# fakealarm_smd.net
KiCad netlist of a schematic drawn in EAGLE
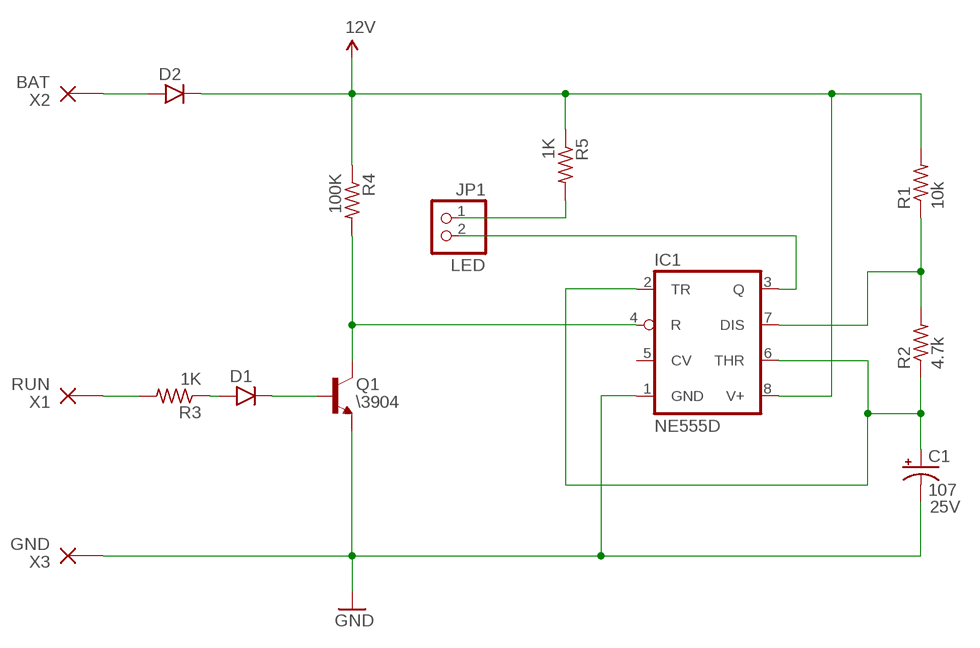
[diagram p0: schematic, sheet 1]

(export (version "E")
  (design (tool "Eeschema 10.0.6"))
  (components
    (comp (ref "C1")
      (value "107")
      (footprint "eagle-import:PANASONIC_C")
      (fields (field (name "VOLTAGE") "25V"))
      (libsource (lib "eagle-import") (part "CPOL-USC"))
    )
    (comp (ref "D1")
      (value "DIODE_SOD123FL")
      (footprint "eagle-import:SOD123FL")
      (libsource (lib "eagle-import") (part "DIODE_SOD123FL"))
    )
    (comp (ref "D2")
      (value "DIODE_SOD123FL")
      (footprint "eagle-import:SOD123FL")
      (libsource (lib "eagle-import") (part "DIODE_SOD123FL"))
    )
    (comp (ref "IC1")
      (value "NE555D")
      (footprint "eagle-import:SO08")
      (libsource (lib "eagle-import") (part "555DNE"))
    )
    (comp (ref "JP1")
      (value "LED")
      (footprint "eagle-import:1X02-S")
      (libsource (lib "eagle-import") (part "PINHD-1X02_2.54-S"))
    )
    (comp (ref "Q1")
      (value "\\3904")
      (footprint "eagle-import:SOT-23")
      (libsource (lib "eagle-import") (part "2N3904SOT23"))
    )
    (comp (ref "R1")
      (value "10k")
      (footprint "eagle-import:R0603")
      (libsource (lib "eagle-import") (part "R-US_R0603"))
    )
    (comp (ref "R2")
      (value "4.7k")
      (footprint "eagle-import:R0603")
      (libsource (lib "eagle-import") (part "R-US_R0603"))
    )
    (comp (ref "R3")
      (value "1K")
      (footprint "eagle-import:R0603")
      (libsource (lib "eagle-import") (part "R-US_R0603"))
    )
    (comp (ref "R4")
      (value "100K")
      (footprint "eagle-import:R0603")
      (libsource (lib "eagle-import") (part "R-US_R0603"))
    )
    (comp (ref "R5")
      (value "1K")
      (footprint "eagle-import:R0603")
      (libsource (lib "eagle-import") (part "R-US_R0603"))
    )
    (comp (ref "X1")
      (value "RUN")
      (footprint "eagle-import:PAD_14GA")
      (libsource (lib "eagle-import") (part "WIREPAD_14GA"))
    )
    (comp (ref "X2")
      (value "BAT")
      (footprint "eagle-import:PAD_14GA")
      (libsource (lib "eagle-import") (part "WIREPAD_14GA"))
    )
    (comp (ref "X3")
      (value "GND")
      (footprint "eagle-import:PAD_14GA")
      (libsource (lib "eagle-import") (part "WIREPAD_14GA"))
    )
  )
  (nets
    (net (code "1") (name "12V") (class "Default")
      (node (ref "D2") (pin "C") (pinfunction "C_C") (pintype "passive"))
      (node (ref "IC1") (pin "8") (pinfunction "V+_8") (pintype "power_in"))
      (node (ref "R1") (pin "2") (pinfunction "2_2") (pintype "passive"))
      (node (ref "R4") (pin "1") (pinfunction "1_1") (pintype "passive"))
      (node (ref "R5") (pin "1") (pinfunction "1_1") (pintype "passive"))
    )
    (net (code "2") (name "GND") (class "Default")
      (node (ref "C1") (pin "-") (pinfunction "-_-") (pintype "passive"))
      (node (ref "IC1") (pin "1") (pinfunction "GND_1") (pintype "power_in"))
      (node (ref "Q1") (pin "2") (pinfunction "E_2") (pintype "passive"))
      (node (ref "X3") (pin "P$1") (pinfunction "P_P$1") (pintype "bidirectional"))
    )
    (net (code "3") (name "Net-(D1-PadA)") (class "Default")
      (node (ref "D1") (pin "A") (pinfunction "A_A") (pintype "passive"))
      (node (ref "R3") (pin "1") (pinfunction "1_1") (pintype "passive"))
    )
    (net (code "4") (name "Net-(IC1-DIS)") (class "Default")
      (node (ref "IC1") (pin "7") (pinfunction "DIS_7") (pintype "input"))
      (node (ref "R1") (pin "1") (pinfunction "1_1") (pintype "passive"))
      (node (ref "R2") (pin "2") (pinfunction "2_2") (pintype "passive"))
    )
    (net (code "5") (name "Net-(IC1-Q)") (class "Default")
      (node (ref "IC1") (pin "3") (pinfunction "Q_3") (pintype "output"))
      (node (ref "JP1") (pin "2") (pinfunction "2_2") (pintype "passive"))
    )
    (net (code "6") (name "Net-(IC1-R)") (class "Default")
      (node (ref "IC1") (pin "4") (pinfunction "R_4") (pintype "input"))
      (node (ref "Q1") (pin "1") (pinfunction "C_1") (pintype "passive"))
      (node (ref "R4") (pin "2") (pinfunction "2_2") (pintype "passive"))
    )
    (net (code "7") (name "Net-(IC1-THR)") (class "Default")
      (node (ref "C1") (pin "+") (pinfunction "+_+") (pintype "passive"))
      (node (ref "IC1") (pin "2") (pinfunction "TR_2") (pintype "input"))
      (node (ref "IC1") (pin "6") (pinfunction "THR_6") (pintype "input"))
      (node (ref "R2") (pin "1") (pinfunction "1_1") (pintype "passive"))
    )
    (net (code "8") (name "Net-(JP1-Pad1)") (class "Default")
      (node (ref "JP1") (pin "1") (pinfunction "1_1") (pintype "passive"))
      (node (ref "R5") (pin "2") (pinfunction "2_2") (pintype "passive"))
    )
    (net (code "9") (name "Net-(Q1-B)") (class "Default")
      (node (ref "D1") (pin "C") (pinfunction "C_C") (pintype "passive"))
      (node (ref "Q1") (pin "3") (pinfunction "B_3") (pintype "passive"))
    )
    (net (code "10") (name "Net-(X1-P)") (class "Default")
      (node (ref "R3") (pin "2") (pinfunction "2_2") (pintype "passive"))
      (node (ref "X1") (pin "P$1") (pinfunction "P_P$1") (pintype "bidirectional"))
    )
    (net (code "11") (name "Net-(X2-P)") (class "Default")
      (node (ref "D2") (pin "A") (pinfunction "A_A") (pintype "passive"))
      (node (ref "X2") (pin "P$1") (pinfunction "P_P$1") (pintype "bidirectional"))
    )
    (net (code "12") (name "unconnected-(IC1-CV-Pad5)") (class "Default")
      (node (ref "IC1") (pin "5") (pinfunction "CV_5") (pintype "input"))
    )
  )
)
